# Motor_PPN7PA12C1_Test_bench.net
KiCad netlist of a schematic drawn in EAGLE
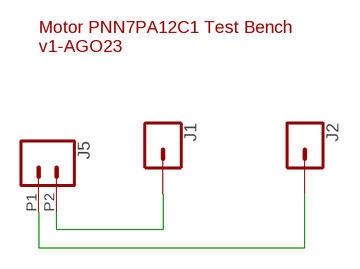
[diagram p0: schematic, sheet 1]

(export (version "E")
  (design (tool "Eeschema 10.0.6"))
  (components
    (comp (ref "J1")
      (value "CONN_01")
      (footprint "eagle-import:1X01")
      (libsource (lib "eagle-import") (part "CONN_01"))
    )
    (comp (ref "J2")
      (value "CONN_01")
      (footprint "eagle-import:1X01")
      (libsource (lib "eagle-import") (part "CONN_01"))
    )
    (comp (ref "J5")
      (value "CONN_022.54MM_SCREWTERM")
      (footprint "eagle-import:1X02_2.54_SCREWTERM")
      (libsource (lib "eagle-import") (part "CONN_022.54MM_SCREWTERM"))
    )
  )
  (nets
    (net (code "1") (name "Net-(J5-1)") (class "Default")
      (node (ref "J2") (pin "1") (pinfunction "1_1") (pintype "passive"))
      (node (ref "J5") (pin "P1") (pinfunction "1_P1") (pintype "passive"))
    )
    (net (code "2") (name "Net-(J5-2)") (class "Default")
      (node (ref "J1") (pin "1") (pinfunction "1_1") (pintype "passive"))
      (node (ref "J5") (pin "P2") (pinfunction "2_P2") (pintype "passive"))
    )
  )
)
